# HirigrandeCHINA_V2_1.net
KiCad netlist of a schematic drawn in EAGLE
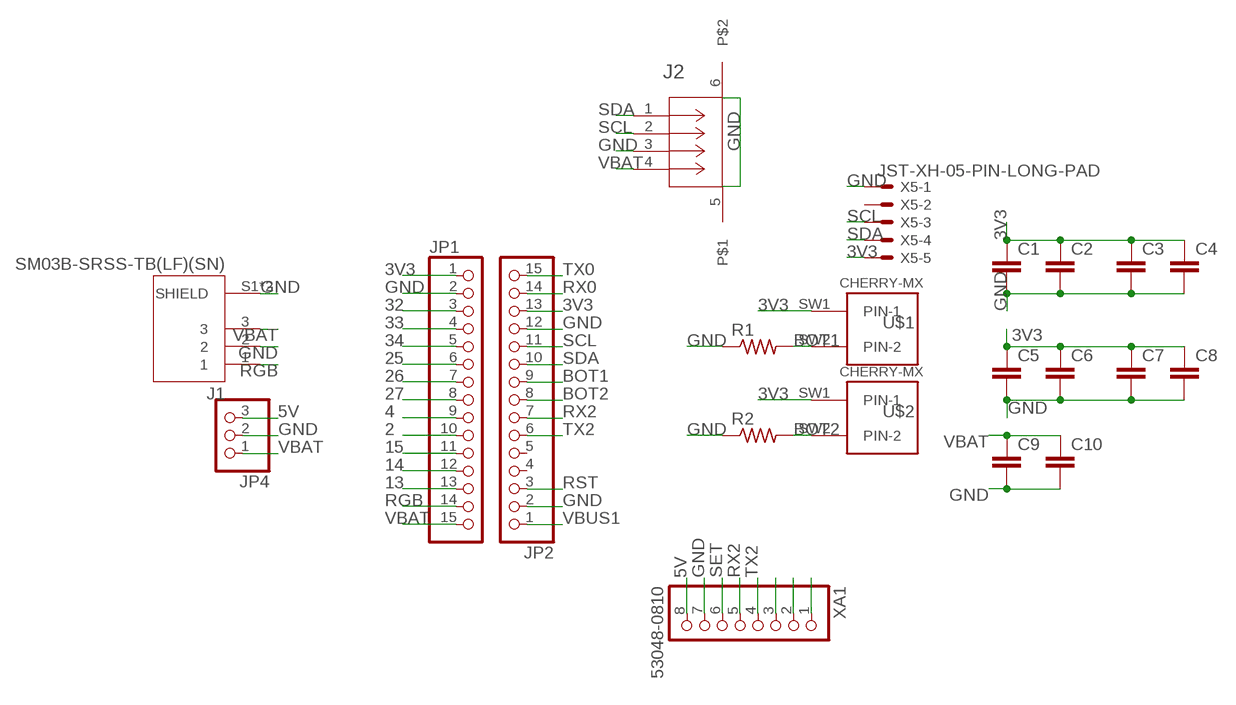
[diagram p0: schematic, sheet 1]

(export (version "E")
  (design (tool "Eeschema 10.0.6"))
  (components
    (comp (ref "C1")
      (value "C-EUC4532")
      (footprint "eagle-import:C4532")
      (libsource (lib "eagle-import") (part "C-EUC4532"))
    )
    (comp (ref "C2")
      (value "C-EUC4532")
      (footprint "eagle-import:C4532")
      (libsource (lib "eagle-import") (part "C-EUC4532"))
    )
    (comp (ref "C3")
      (value "C-EUC4532")
      (footprint "eagle-import:C4532")
      (libsource (lib "eagle-import") (part "C-EUC4532"))
    )
    (comp (ref "C4")
      (value "C-EUC4532")
      (footprint "eagle-import:C4532")
      (libsource (lib "eagle-import") (part "C-EUC4532"))
    )
    (comp (ref "C5")
      (value "C-EUC4532")
      (footprint "eagle-import:C4532")
      (libsource (lib "eagle-import") (part "C-EUC4532"))
    )
    (comp (ref "C6")
      (value "C-EUC4532")
      (footprint "eagle-import:C4532")
      (libsource (lib "eagle-import") (part "C-EUC4532"))
    )
    (comp (ref "C7")
      (value "C-EUC4532")
      (footprint "eagle-import:C4532")
      (libsource (lib "eagle-import") (part "C-EUC4532"))
    )
    (comp (ref "C8")
      (value "C-EUC4532")
      (footprint "eagle-import:C4532")
      (libsource (lib "eagle-import") (part "C-EUC4532"))
    )
    (comp (ref "C9")
      (value "C-EUC4532")
      (footprint "eagle-import:C4532")
      (libsource (lib "eagle-import") (part "C-EUC4532"))
    )
    (comp (ref "C10")
      (value "C-EUC4532")
      (footprint "eagle-import:C4532")
      (libsource (lib "eagle-import") (part "C-EUC4532"))
    )
    (comp (ref "J1")
      (value "SM03B-SRSS-TB(LF)(SN)")
      (footprint "eagle-import:JST_SM03B-SRSS-TB(LF)(SN)")
      (fields (field (name "MF") "JST Sales America Inc."))
      (libsource (lib "eagle-import") (part "SM03B-SRSS-TB(LF)(SN)"))
    )
    (comp (ref "J2")
      (value "SM04B-SRSS-TB")
      (footprint "eagle-import:CONN_SM04B-SRSS-TB_JST")
      (fields (field (name "MF") "JST Sales"))
      (libsource (lib "eagle-import") (part "SM04B-SRSS-TB"))
    )
    (comp (ref "JP1")
      (value "PINHD-1X15")
      (footprint "eagle-import:1X15")
      (libsource (lib "eagle-import") (part "PINHD-1X15"))
    )
    (comp (ref "JP2")
      (value "PINHD-1X15")
      (footprint "eagle-import:1X15")
      (libsource (lib "eagle-import") (part "PINHD-1X15"))
    )
    (comp (ref "JP4")
      (value "PINHD-1X3")
      (footprint "eagle-import:1X03")
      (libsource (lib "eagle-import") (part "PINHD-1X3"))
    )
    (comp (ref "R1")
      (value "R-US_0204/7")
      (footprint "eagle-import:0204_7")
      (libsource (lib "eagle-import") (part "R-US_0204/7"))
    )
    (comp (ref "R2")
      (value "R-US_0204/7")
      (footprint "eagle-import:0204_7")
      (libsource (lib "eagle-import") (part "R-US_0204/7"))
    )
    (comp (ref "U$1")
      (value "CHERRY-MX")
      (footprint "eagle-import:CHERRY-MX")
      (libsource (lib "eagle-import") (part "CHERRY-MX"))
    )
    (comp (ref "U$2")
      (value "CHERRY-MX")
      (footprint "eagle-import:CHERRY-MX")
      (libsource (lib "eagle-import") (part "CHERRY-MX"))
    )
    (comp (ref "X5")
      (value "JST-XH-05-PIN-LONG-PAD")
      (footprint "eagle-import:JST-XH-05-PACKAGE-LONG-PAD")
      (libsource (lib "eagle-import") (part "JST-XH-05-PIN-LONG-PAD"))
    )
    (comp (ref "XA1")
      (value "53048-0810")
      (footprint "eagle-import:MOLEX_53048-0810")
      (fields (field (name "MF") "Molex"))
      (libsource (lib "eagle-import") (part "53048-0810"))
    )
  )
  (nets
    (net (code "1") (name "/2") (class "Default")
      (node (ref "JP1") (pin "10") (pinfunction "10_10") (pintype "passive"))
    )
    (net (code "2") (name "/3V3") (class "Default")
      (node (ref "C1") (pin "1") (pinfunction "1_1") (pintype "passive"))
      (node (ref "C2") (pin "1") (pinfunction "1_1") (pintype "passive"))
      (node (ref "C3") (pin "1") (pinfunction "1_1") (pintype "passive"))
      (node (ref "C4") (pin "1") (pinfunction "1_1") (pintype "passive"))
      (node (ref "C5") (pin "1") (pinfunction "1_1") (pintype "passive"))
      (node (ref "C6") (pin "1") (pinfunction "1_1") (pintype "passive"))
      (node (ref "C7") (pin "1") (pinfunction "1_1") (pintype "passive"))
      (node (ref "C8") (pin "1") (pinfunction "1_1") (pintype "passive"))
      (node (ref "JP1") (pin "1") (pinfunction "1_1") (pintype "passive"))
      (node (ref "JP2") (pin "13") (pinfunction "13_13") (pintype "passive"))
      (node (ref "U$1") (pin "SW1") (pinfunction "PIN-1_SW1") (pintype "bidirectional"))
      (node (ref "U$2") (pin "SW1") (pinfunction "PIN-1_SW1") (pintype "bidirectional"))
      (node (ref "X5") (pin "5") (pinfunction "S_5") (pintype "passive"))
    )
    (net (code "3") (name "/4") (class "Default")
      (node (ref "JP1") (pin "9") (pinfunction "9_9") (pintype "passive"))
    )
    (net (code "4") (name "/5V") (class "Default")
      (node (ref "JP4") (pin "3") (pinfunction "3_3") (pintype "passive"))
      (node (ref "XA1") (pin "8") (pinfunction "8_8") (pintype "passive"))
    )
    (net (code "5") (name "/13") (class "Default")
      (node (ref "JP1") (pin "13") (pinfunction "13_13") (pintype "passive"))
    )
    (net (code "6") (name "/14") (class "Default")
      (node (ref "JP1") (pin "12") (pinfunction "12_12") (pintype "passive"))
    )
    (net (code "7") (name "/15") (class "Default")
      (node (ref "JP1") (pin "11") (pinfunction "11_11") (pintype "passive"))
    )
    (net (code "8") (name "/25") (class "Default")
      (node (ref "JP1") (pin "6") (pinfunction "6_6") (pintype "passive"))
    )
    (net (code "9") (name "/26") (class "Default")
      (node (ref "JP1") (pin "7") (pinfunction "7_7") (pintype "passive"))
    )
    (net (code "10") (name "/27") (class "Default")
      (node (ref "JP1") (pin "8") (pinfunction "8_8") (pintype "passive"))
    )
    (net (code "11") (name "/32") (class "Default")
      (node (ref "JP1") (pin "3") (pinfunction "3_3") (pintype "passive"))
    )
    (net (code "12") (name "/33") (class "Default")
      (node (ref "JP1") (pin "4") (pinfunction "4_4") (pintype "passive"))
    )
    (net (code "13") (name "/34") (class "Default")
      (node (ref "JP1") (pin "5") (pinfunction "5_5") (pintype "passive"))
    )
    (net (code "14") (name "/BOT1") (class "Default")
      (node (ref "JP2") (pin "9") (pinfunction "9_9") (pintype "passive"))
      (node (ref "R1") (pin "2") (pinfunction "2_2") (pintype "passive"))
      (node (ref "U$1") (pin "SW2") (pinfunction "PIN-2_SW2") (pintype "bidirectional"))
    )
    (net (code "15") (name "/BOT2") (class "Default")
      (node (ref "JP2") (pin "8") (pinfunction "8_8") (pintype "passive"))
      (node (ref "R2") (pin "2") (pinfunction "2_2") (pintype "passive"))
      (node (ref "U$2") (pin "SW2") (pinfunction "PIN-2_SW2") (pintype "bidirectional"))
    )
    (net (code "16") (name "/GND") (class "Default")
      (node (ref "C1") (pin "2") (pinfunction "2_2") (pintype "passive"))
      (node (ref "C10") (pin "2") (pinfunction "2_2") (pintype "passive"))
      (node (ref "C2") (pin "2") (pinfunction "2_2") (pintype "passive"))
      (node (ref "C3") (pin "2") (pinfunction "2_2") (pintype "passive"))
      (node (ref "C4") (pin "2") (pinfunction "2_2") (pintype "passive"))
      (node (ref "C5") (pin "2") (pinfunction "2_2") (pintype "passive"))
      (node (ref "C6") (pin "2") (pinfunction "2_2") (pintype "passive"))
      (node (ref "C7") (pin "2") (pinfunction "2_2") (pintype "passive"))
      (node (ref "C8") (pin "2") (pinfunction "2_2") (pintype "passive"))
      (node (ref "C9") (pin "2") (pinfunction "2_2") (pintype "passive"))
      (node (ref "J1") (pin "2") (pinfunction "2_2") (pintype "passive"))
      (node (ref "J1") (pin "S1") (pinfunction "SHIELD_S1") (pintype "passive"))
      (node (ref "J1") (pin "S2") (pinfunction "SHIELD_S2") (pintype "passive"))
      (node (ref "J2") (pin "3") (pinfunction "3_3") (pintype "passive"))
      (node (ref "J2") (pin "5") (pinfunction "P$1_5") (pintype "bidirectional"))
      (node (ref "J2") (pin "6") (pinfunction "P$2_6") (pintype "bidirectional"))
      (node (ref "JP1") (pin "2") (pinfunction "2_2") (pintype "passive"))
      (node (ref "JP2") (pin "12") (pinfunction "12_12") (pintype "passive"))
      (node (ref "JP2") (pin "2") (pinfunction "2_2") (pintype "passive"))
      (node (ref "JP4") (pin "2") (pinfunction "2_2") (pintype "passive"))
      (node (ref "R1") (pin "1") (pinfunction "1_1") (pintype "passive"))
      (node (ref "R2") (pin "1") (pinfunction "1_1") (pintype "passive"))
      (node (ref "X5") (pin "1") (pinfunction "S_1") (pintype "passive"))
      (node (ref "XA1") (pin "7") (pinfunction "7_7") (pintype "passive"))
    )
    (net (code "17") (name "/RGB") (class "Default")
      (node (ref "J1") (pin "1") (pinfunction "1_1") (pintype "passive"))
      (node (ref "JP1") (pin "14") (pinfunction "14_14") (pintype "passive"))
    )
    (net (code "18") (name "/RST") (class "Default")
      (node (ref "JP2") (pin "3") (pinfunction "3_3") (pintype "passive"))
    )
    (net (code "19") (name "/RX0") (class "Default")
      (node (ref "JP2") (pin "14") (pinfunction "14_14") (pintype "passive"))
    )
    (net (code "20") (name "/RX2") (class "Default")
      (node (ref "JP2") (pin "7") (pinfunction "7_7") (pintype "passive"))
      (node (ref "XA1") (pin "5") (pinfunction "5_5") (pintype "passive"))
    )
    (net (code "21") (name "/SCL") (class "Default")
      (node (ref "J2") (pin "2") (pinfunction "2_2") (pintype "passive"))
      (node (ref "JP2") (pin "11") (pinfunction "11_11") (pintype "passive"))
      (node (ref "X5") (pin "3") (pinfunction "S_3") (pintype "passive"))
    )
    (net (code "22") (name "/SDA") (class "Default")
      (node (ref "J2") (pin "1") (pinfunction "1_1") (pintype "passive"))
      (node (ref "JP2") (pin "10") (pinfunction "10_10") (pintype "passive"))
      (node (ref "X5") (pin "4") (pinfunction "S_4") (pintype "passive"))
    )
    (net (code "23") (name "/SET") (class "Default")
      (node (ref "XA1") (pin "6") (pinfunction "6_6") (pintype "passive"))
    )
    (net (code "24") (name "/TX0") (class "Default")
      (node (ref "JP2") (pin "15") (pinfunction "15_15") (pintype "passive"))
    )
    (net (code "25") (name "/TX2") (class "Default")
      (node (ref "JP2") (pin "6") (pinfunction "6_6") (pintype "passive"))
      (node (ref "XA1") (pin "4") (pinfunction "4_4") (pintype "passive"))
    )
    (net (code "26") (name "/VBAT") (class "Default")
      (node (ref "C10") (pin "1") (pinfunction "1_1") (pintype "passive"))
      (node (ref "C9") (pin "1") (pinfunction "1_1") (pintype "passive"))
      (node (ref "J1") (pin "3") (pinfunction "3_3") (pintype "passive"))
      (node (ref "J2") (pin "4") (pinfunction "4_4") (pintype "passive"))
      (node (ref "JP1") (pin "15") (pinfunction "15_15") (pintype "passive"))
      (node (ref "JP4") (pin "1") (pinfunction "1_1") (pintype "passive"))
    )
    (net (code "27") (name "/VBUS1") (class "Default")
      (node (ref "JP2") (pin "1") (pinfunction "1_1") (pintype "passive"))
    )
    (net (code "28") (name "unconnected-(JP2-Pad4)") (class "Default")
      (node (ref "JP2") (pin "4") (pinfunction "4_4") (pintype "passive"))
    )
    (net (code "29") (name "unconnected-(JP2-Pad5)") (class "Default")
      (node (ref "JP2") (pin "5") (pinfunction "5_5") (pintype "passive"))
    )
    (net (code "30") (name "unconnected-(X5B-S-Pad2)") (class "Default")
      (node (ref "X5") (pin "2") (pinfunction "S_2") (pintype "passive"))
    )
    (net (code "31") (name "unconnected-(XA1-Pad1)") (class "Default")
      (node (ref "XA1") (pin "1") (pinfunction "1_1") (pintype "passive"))
    )
    (net (code "32") (name "unconnected-(XA1-Pad2)") (class "Default")
      (node (ref "XA1") (pin "2") (pinfunction "2_2") (pintype "passive"))
    )
    (net (code "33") (name "unconnected-(XA1-Pad3)") (class "Default")
      (node (ref "XA1") (pin "3") (pinfunction "3_3") (pintype "passive"))
    )
  )
)
